# daytripper_pogo.net
KiCad netlist of a schematic drawn in EAGLE
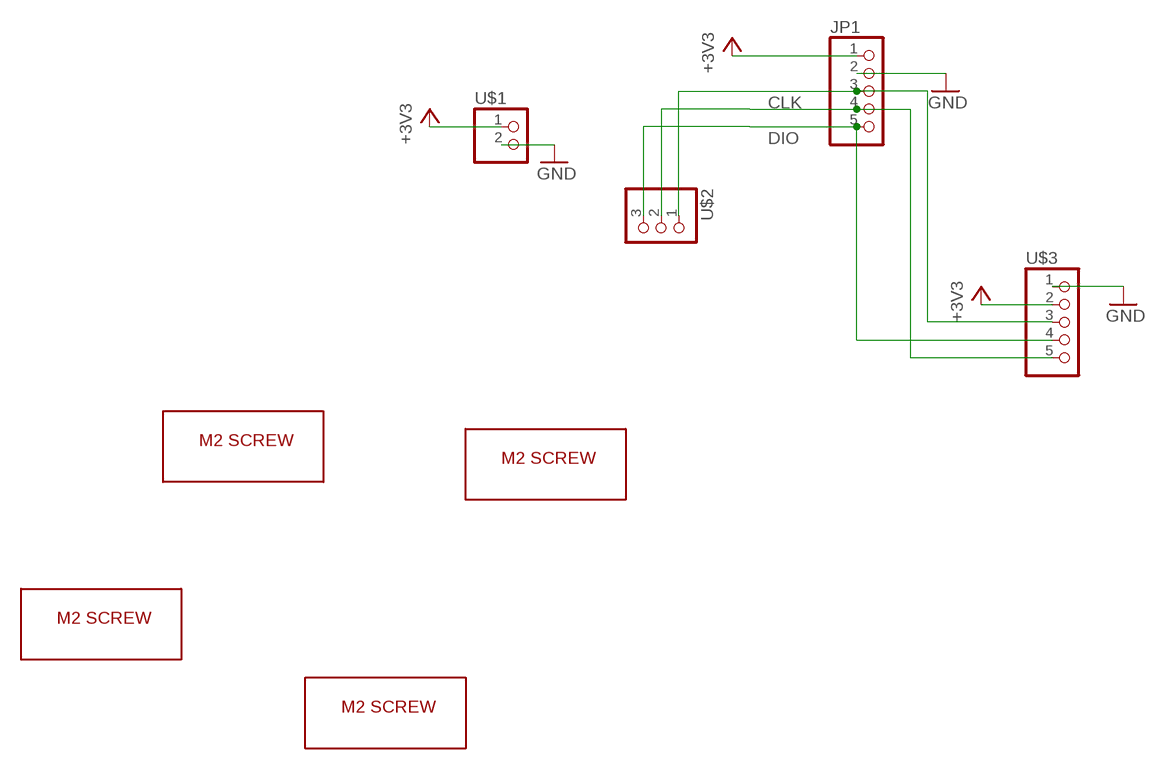
[diagram p0: schematic, sheet 1]

(export (version "E")
  (design (tool "Eeschema 10.0.6"))
  (components
    (comp (ref "JP1")
      (value "PINHD-1X5")
      (footprint "eagle-import:1X05")
      (libsource (lib "eagle-import") (part "PINHD-1X5"))
    )
    (comp (ref "U$1")
      (value "POGO-1X2")
      (footprint "eagle-import:1X02")
      (libsource (lib "eagle-import") (part "POGO-1X2"))
    )
    (comp (ref "U$2")
      (value "POGO-1X3")
      (footprint "eagle-import:1X03")
      (libsource (lib "eagle-import") (part "POGO-1X3"))
    )
    (comp (ref "U$3")
      (value "POGO-1X5")
      (footprint "eagle-import:1X05")
      (libsource (lib "eagle-import") (part "POGO-1X5"))
    )
    (comp (ref "U$4")
      (value "M2_SCREW_DEV")
      (footprint "eagle-import:M2_SCREW_FOOT")
      (libsource (lib "eagle-import") (part "M2_SCREW_DEV"))
    )
    (comp (ref "U$12")
      (value "M2_SCREW_DEV")
      (footprint "eagle-import:M2_SCREW_FOOT")
      (libsource (lib "eagle-import") (part "M2_SCREW_DEV"))
    )
    (comp (ref "U$13")
      (value "M2_SCREW_DEV")
      (footprint "eagle-import:M2_SCREW_FOOT")
      (libsource (lib "eagle-import") (part "M2_SCREW_DEV"))
    )
    (comp (ref "U$14")
      (value "M2_SCREW_DEV")
      (footprint "eagle-import:M2_SCREW_FOOT")
      (libsource (lib "eagle-import") (part "M2_SCREW_DEV"))
    )
  )
  (nets
    (net (code "1") (name "+3V3") (class "Default")
      (node (ref "JP1") (pin "1") (pinfunction "1_1") (pintype "passive"))
      (node (ref "U$1") (pin "1") (pinfunction "1_1") (pintype "passive"))
      (node (ref "U$3") (pin "2") (pinfunction "2_2") (pintype "passive"))
    )
    (net (code "2") (name "/CLK") (class "Default")
      (node (ref "JP1") (pin "4") (pinfunction "4_4") (pintype "passive"))
      (node (ref "U$2") (pin "2") (pinfunction "2_2") (pintype "passive"))
      (node (ref "U$3") (pin "5") (pinfunction "5_5") (pintype "passive"))
    )
    (net (code "3") (name "/DIO") (class "Default")
      (node (ref "JP1") (pin "5") (pinfunction "5_5") (pintype "passive"))
      (node (ref "U$2") (pin "3") (pinfunction "3_3") (pintype "passive"))
      (node (ref "U$3") (pin "4") (pinfunction "4_4") (pintype "passive"))
    )
    (net (code "4") (name "GND") (class "Default")
      (node (ref "JP1") (pin "2") (pinfunction "2_2") (pintype "passive"))
      (node (ref "U$1") (pin "2") (pinfunction "2_2") (pintype "passive"))
      (node (ref "U$3") (pin "1") (pinfunction "1_1") (pintype "passive"))
    )
    (net (code "5") (name "Net-(JP1-Pad3)") (class "Default")
      (node (ref "JP1") (pin "3") (pinfunction "3_3") (pintype "passive"))
      (node (ref "U$2") (pin "1") (pinfunction "1_1") (pintype "passive"))
      (node (ref "U$3") (pin "3") (pinfunction "3_3") (pintype "passive"))
    )
  )
)
